# RTI-Dome-eth.net
KiCad netlist of a schematic drawn in EAGLE
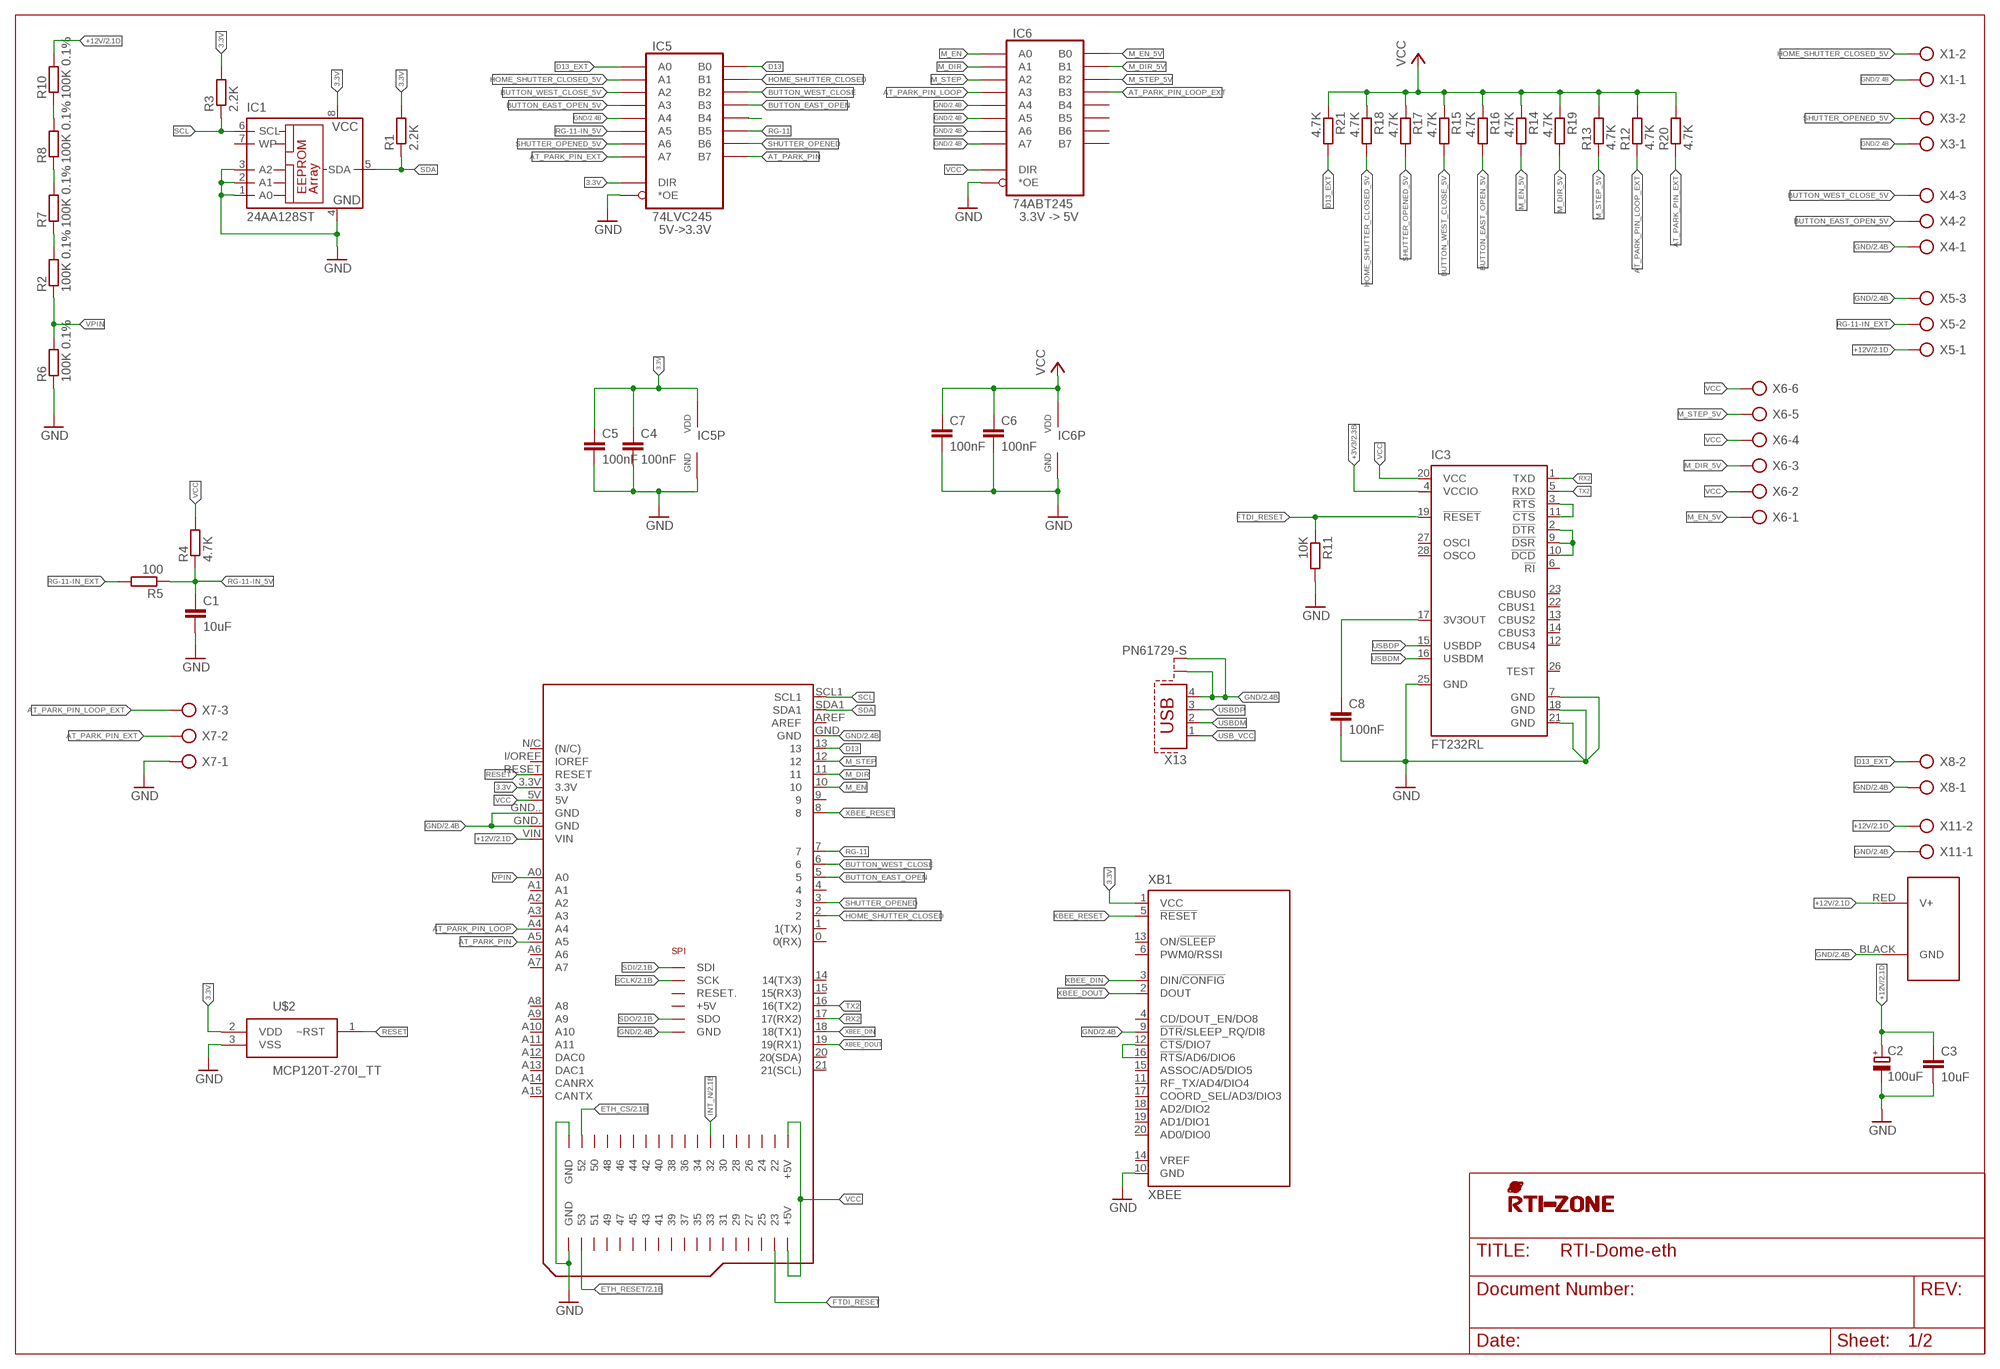
[diagram p0: schematic, sheet 1]
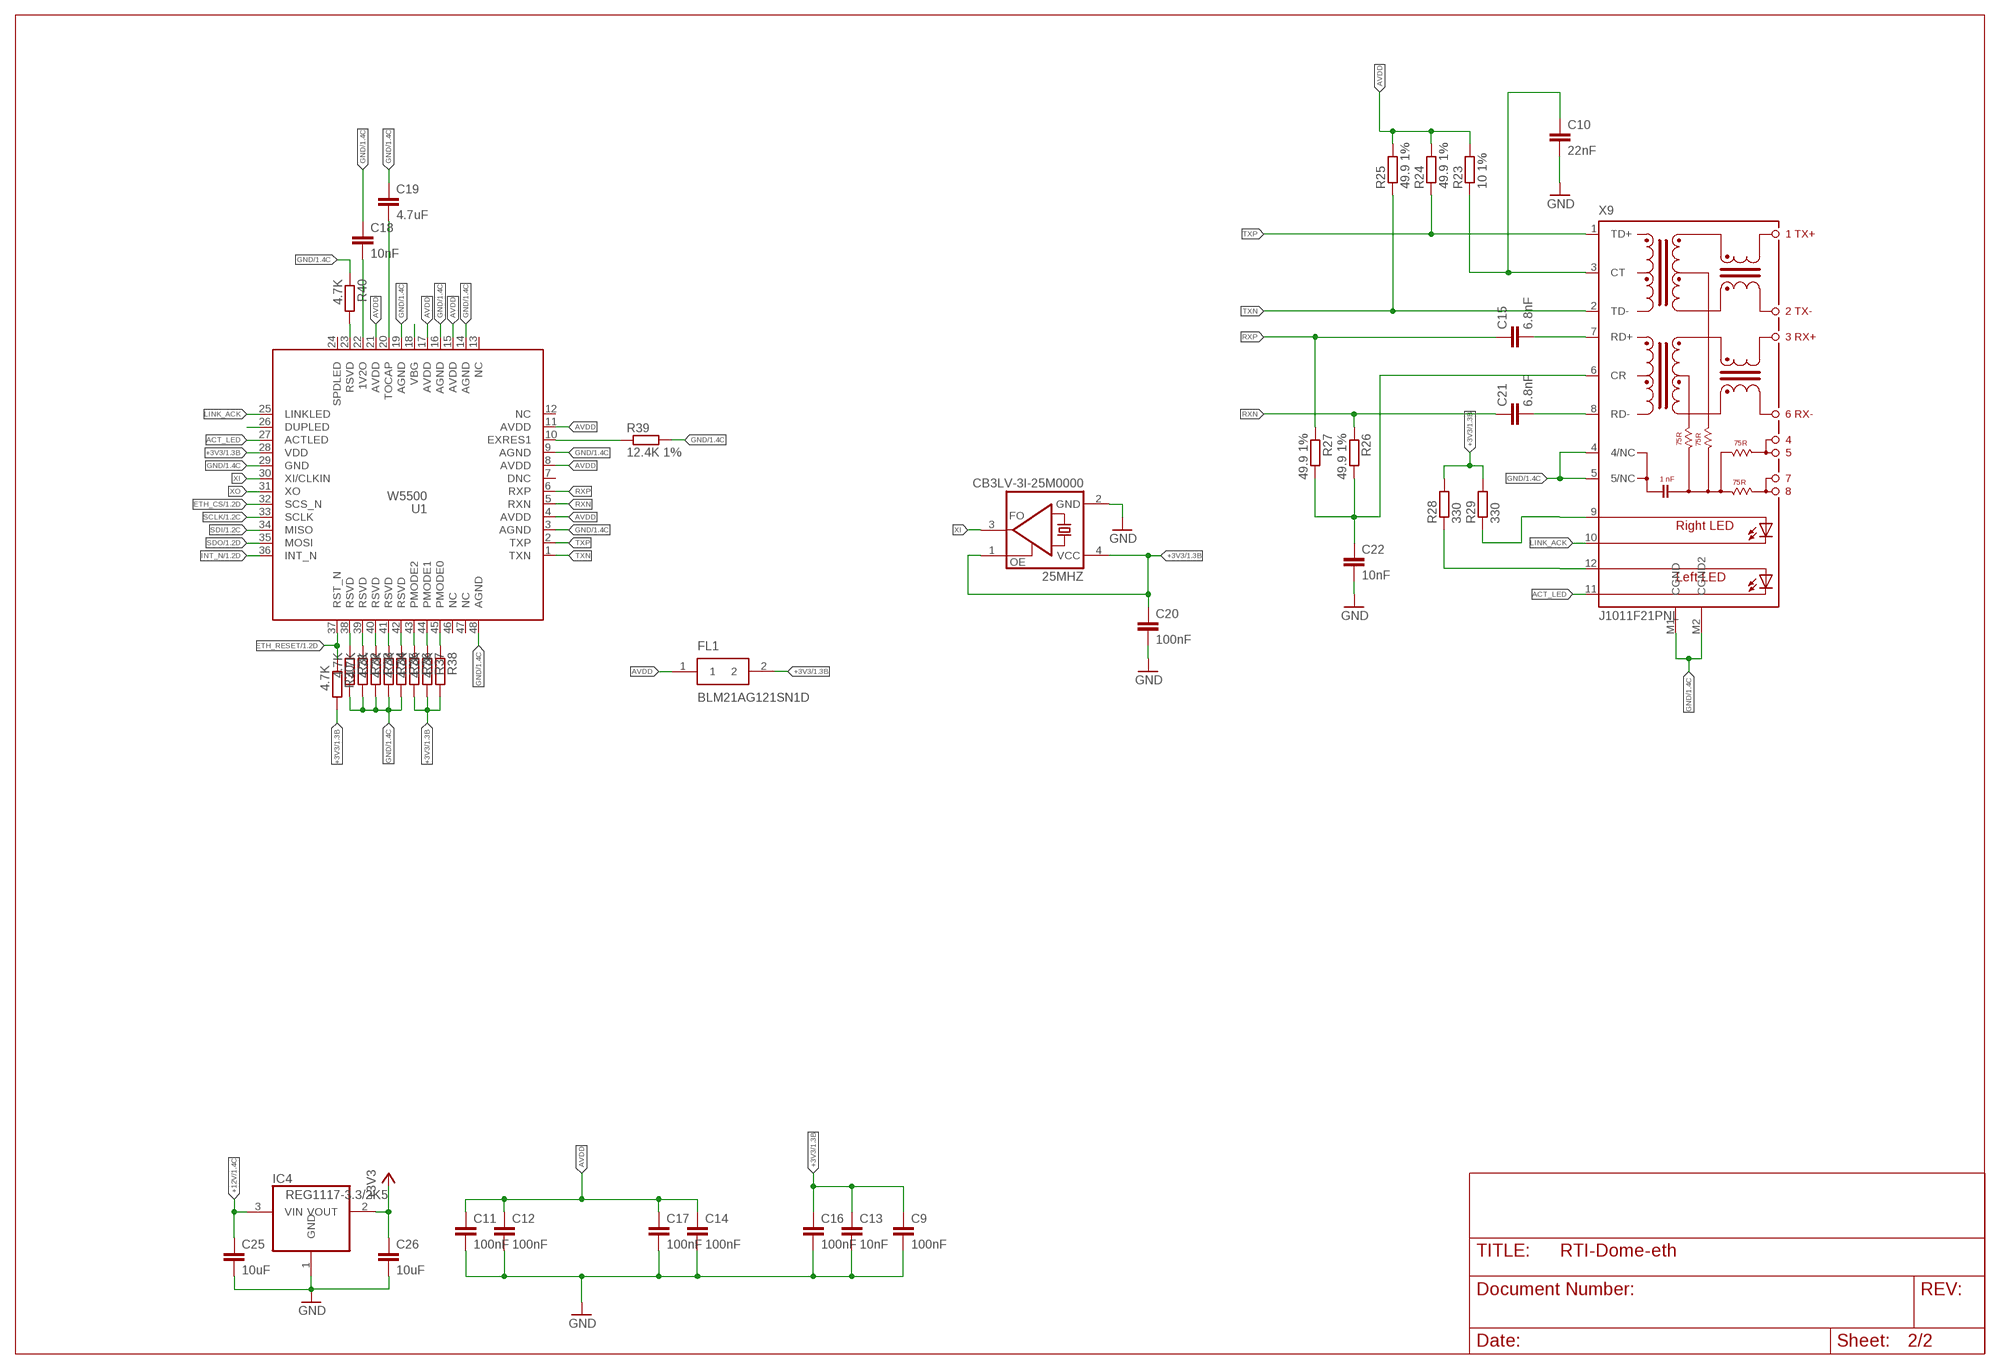
[diagram p1: schematic, sheet 2]

(export (version "E")
  (design (tool "Eeschema 10.0.6"))
  (components
    (comp (ref "25MHZ")
      (value "CB3LV-3I-25M0000")
      (footprint "eagle-import:SMD-7050_4P")
      (libsource (lib "eagle-import") (part "CB3LV-OSCILATOR"))
    )
    (comp (ref "C9")
      (value "100nF")
      (footprint "eagle-import:C0805")
      (fields (field (name "MPN") "0805YD104KAT2A"))
      (libsource (lib "eagle-import") (part "C-EU'0805'"))
    )
    (comp (ref "C10")
      (value "22nF")
      (footprint "eagle-import:C0805")
      (fields (field (name "MPN") "CC0805JRX7R8BB223"))
      (libsource (lib "eagle-import") (part "C-EU'0805'"))
    )
    (comp (ref "C11")
      (value "100nF")
      (footprint "eagle-import:C0805")
      (fields (field (name "MPN") "0805YD104KAT2A"))
      (libsource (lib "eagle-import") (part "C-EU'0805'"))
    )
    (comp (ref "C12")
      (value "100nF")
      (footprint "eagle-import:C0805")
      (fields (field (name "MPN") "0805YD104KAT2A"))
      (libsource (lib "eagle-import") (part "C-EU'0805'"))
    )
    (comp (ref "C13")
      (value "10nF")
      (footprint "eagle-import:C0805")
      (fields (field (name "MPN") " CC0805KRX7R9BB103"))
      (libsource (lib "eagle-import") (part "C-EU'0805'"))
    )
    (comp (ref "C14")
      (value "100nF")
      (footprint "eagle-import:C0805")
      (fields (field (name "MPN") "0805YD104KAT2A"))
      (libsource (lib "eagle-import") (part "C-EU'0805'"))
    )
    (comp (ref "C15")
      (value "6.8nF")
      (footprint "eagle-import:C0805")
      (fields (field (name "MPN") "C0805C682F4HACTU"))
      (libsource (lib "eagle-import") (part "C-EU'0805'"))
    )
    (comp (ref "C16")
      (value "100nF")
      (footprint "eagle-import:C0805")
      (fields (field (name "MPN") "0805YD104KAT2A"))
      (libsource (lib "eagle-import") (part "C-EU'0805'"))
    )
    (comp (ref "C17")
      (value "100nF")
      (footprint "eagle-import:C0805")
      (fields (field (name "MPN") "0805YD104KAT2A"))
      (libsource (lib "eagle-import") (part "C-EU'0805'"))
    )
    (comp (ref "C18")
      (value "10nF")
      (footprint "eagle-import:C0805")
      (fields (field (name "MPN") " CC0805KRX7R9BB103"))
      (libsource (lib "eagle-import") (part "C-EU'0805'"))
    )
    (comp (ref "C19")
      (value "4.7uF")
      (footprint "eagle-import:C0805")
      (fields (field (name "MPN") "C0805C475J3RACTU"))
      (libsource (lib "eagle-import") (part "C-EU'0805'"))
    )
    (comp (ref "C20")
      (value "100nF")
      (footprint "eagle-import:C0805")
      (fields (field (name "MPN") "0805YD104KAT2A"))
      (libsource (lib "eagle-import") (part "C-EU'0805'"))
    )
    (comp (ref "C21")
      (value "6.8nF")
      (footprint "eagle-import:C0805")
      (fields (field (name "MPN") "C0805C682F4HACTU"))
      (libsource (lib "eagle-import") (part "C-EU'0805'"))
    )
    (comp (ref "C22")
      (value "10nF")
      (footprint "eagle-import:C0805")
      (fields (field (name "MPN") " CC0805KRX7R9BB103"))
      (libsource (lib "eagle-import") (part "C-EU'0805'"))
    )
    (comp (ref "C25")
      (value "10uF")
      (footprint "eagle-import:C0805")
      (fields (field (name "MPN") "CC0805KKX5R8BB106"))
      (libsource (lib "eagle-import") (part "C-EU'0805'"))
    )
    (comp (ref "C26")
      (value "10uF")
      (footprint "eagle-import:C0805")
      (fields (field (name "MPN") "CC0805KKX5R8BB106"))
      (libsource (lib "eagle-import") (part "C-EU'0805'"))
    )
    (comp (ref "FL1")
      (value "BLM21AG121SN1D")
      (footprint "eagle-import:L0805")
      (libsource (lib "eagle-import") (part "BLM21AG121SN1D"))
    )
    (comp (ref "IC4")
      (value "REG1117-3.3/2K5")
      (footprint "eagle-import:SOT223")
      (fields (field (name "MPN") "REG1117") (field (name "MPN_1") "REG1117-3.3/2K5"))
      (libsource (lib "eagle-import") (part "REG1117"))
    )
    (comp (ref "R23")
      (value "10 1%")
      (footprint "eagle-import:R0805")
      (fields (field (name "MPN") "RT0805FRE1310RL"))
      (libsource (lib "eagle-import") (part "R-EU'0805'"))
    )
    (comp (ref "R24")
      (value "49.9 1%")
      (footprint "eagle-import:R0805")
      (fields (field (name "MPN") "RC0805FR-0749R9L"))
      (libsource (lib "eagle-import") (part "R-EU'0805'"))
    )
    (comp (ref "R25")
      (value "49.9 1%")
      (footprint "eagle-import:R0805")
      (fields (field (name "MPN") "RC0805FR-0749R9L"))
      (libsource (lib "eagle-import") (part "R-EU'0805'"))
    )
    (comp (ref "R26")
      (value "49.9 1%")
      (footprint "eagle-import:R0805")
      (fields (field (name "MPN") "RC0805FR-0749R9L"))
      (libsource (lib "eagle-import") (part "R-EU'0805'"))
    )
    (comp (ref "R27")
      (value "49.9 1%")
      (footprint "eagle-import:R0805")
      (fields (field (name "MPN") "RC0805FR-0749R9L"))
      (libsource (lib "eagle-import") (part "R-EU'0805'"))
    )
    (comp (ref "R28")
      (value "330")
      (footprint "eagle-import:R0805")
      (fields (field (name "MPN") " RC0805JR-07330RL"))
      (libsource (lib "eagle-import") (part "R-EU'0805'"))
    )
    (comp (ref "R29")
      (value "330")
      (footprint "eagle-import:R0805")
      (fields (field (name "MPN") " RC0805JR-07330RL"))
      (libsource (lib "eagle-import") (part "R-EU'0805'"))
    )
    (comp (ref "R30")
      (value "4.7K")
      (footprint "eagle-import:R0805")
      (fields (field (name "MPN") "RT0805FRE074K7L"))
      (libsource (lib "eagle-import") (part "R-EU'0805'"))
    )
    (comp (ref "R31")
      (value "4.7K")
      (footprint "eagle-import:R0805")
      (fields (field (name "MPN") "RT0805FRE074K7L"))
      (libsource (lib "eagle-import") (part "R-EU'0805'"))
    )
    (comp (ref "R32")
      (value "4.7K")
      (footprint "eagle-import:R0805")
      (fields (field (name "MPN") "RT0805FRE074K7L"))
      (libsource (lib "eagle-import") (part "R-EU'0805'"))
    )
    (comp (ref "R33")
      (value "4.7K")
      (footprint "eagle-import:R0805")
      (fields (field (name "MPN") "RT0805FRE074K7L"))
      (libsource (lib "eagle-import") (part "R-EU'0805'"))
    )
    (comp (ref "R34")
      (value "4.7K")
      (footprint "eagle-import:R0805")
      (fields (field (name "MPN") "RT0805FRE074K7L"))
      (libsource (lib "eagle-import") (part "R-EU'0805'"))
    )
    (comp (ref "R35")
      (value "4.7K")
      (footprint "eagle-import:R0805")
      (fields (field (name "MPN") "RT0805FRE074K7L"))
      (libsource (lib "eagle-import") (part "R-EU'0805'"))
    )
    (comp (ref "R36")
      (value "4.7K")
      (footprint "eagle-import:R0805")
      (fields (field (name "MPN") "RT0805FRE074K7L"))
      (libsource (lib "eagle-import") (part "R-EU'0805'"))
    )
    (comp (ref "R37")
      (value "4.7K")
      (footprint "eagle-import:R0805")
      (fields (field (name "MPN") "RT0805FRE074K7L"))
      (libsource (lib "eagle-import") (part "R-EU'0805'"))
    )
    (comp (ref "R38")
      (value "4.7K")
      (footprint "eagle-import:R0805")
      (fields (field (name "MPN") "RT0805FRE074K7L"))
      (libsource (lib "eagle-import") (part "R-EU'0805'"))
    )
    (comp (ref "R39")
      (value "12.4K 1%")
      (footprint "eagle-import:R0805")
      (fields (field (name "MPN") "RC0805FR-0712K4L"))
      (libsource (lib "eagle-import") (part "R-EU'0805'"))
    )
    (comp (ref "R40")
      (value "4.7K")
      (footprint "eagle-import:R0805")
      (fields (field (name "MPN") "RT0805FRE074K7L"))
      (libsource (lib "eagle-import") (part "R-EU'0805'"))
    )
    (comp (ref "U1")
      (value "W5500")
      (footprint "eagle-import:LQFP48")
      (libsource (lib "eagle-import") (part "W5500"))
    )
    (comp (ref "X9")
      (value "J1011F21PNL")
      (footprint "eagle-import:J1011F21PNL")
      (fields (field (name "MPN") "J1011F21PNL"))
      (libsource (lib "eagle-import") (part "J1011F21PNL"))
    )
    (comp (ref "C1")
      (value "10uF")
      (footprint "eagle-import:C0805")
      (fields (field (name "MPN") "CC0805KKX5R8BB106"))
      (libsource (lib "eagle-import") (part "C-EU'0805'"))
    )
    (comp (ref "C2")
      (value "100uF")
      (footprint "eagle-import:UD-10X10_NICHICON")
      (fields (field (name "MPN") "MAL215099804E3"))
      (libsource (lib "eagle-import") (part "CPOL-EU"))
    )
    (comp (ref "C3")
      (value "10uF")
      (footprint "eagle-import:C0805")
      (fields (field (name "MPN") "CC0805KKX5R8BB106"))
      (libsource (lib "eagle-import") (part "C-EU'0805'"))
    )
    (comp (ref "C4")
      (value "100nF")
      (footprint "eagle-import:C0805")
      (fields (field (name "MPN") "0805YD104KAT2A"))
      (libsource (lib "eagle-import") (part "C-EU'0805'"))
    )
    (comp (ref "C5")
      (value "100nF")
      (footprint "eagle-import:C0805")
      (fields (field (name "MPN") "0805YD104KAT2A"))
      (libsource (lib "eagle-import") (part "C-EU'0805'"))
    )
    (comp (ref "C6")
      (value "100nF")
      (footprint "eagle-import:C0805")
      (fields (field (name "MPN") "0805YD104KAT2A"))
      (libsource (lib "eagle-import") (part "C-EU'0805'"))
    )
    (comp (ref "C7")
      (value "100nF")
      (footprint "eagle-import:C0805")
      (fields (field (name "MPN") "0805YD104KAT2A"))
      (libsource (lib "eagle-import") (part "C-EU'0805'"))
    )
    (comp (ref "C8")
      (value "100nF")
      (footprint "eagle-import:C0805")
      (fields (field (name "MPN") "0805YD104KAT2A"))
      (libsource (lib "eagle-import") (part "C-EU'0805'"))
    )
    (comp (ref "IC1")
      (value "24AA128ST")
      (footprint "eagle-import:TSSOP8")
      (fields (field (name "MF") "MICROCHIP") (field (name "MPN") "24AA128-I/ST"))
      (libsource (lib "eagle-import") (part "24STAA128"))
    )
    (comp (ref "IC3")
      (value "FT232RL")
      (footprint "eagle-import:SSOP28")
      (fields (field (name "MPN") "FT232RL-REEL"))
      (libsource (lib "eagle-import") (part "FT232RL"))
    )
    (comp (ref "IC5")
      (value "74LVC245")
      (footprint "eagle-import:TSSOP20")
      (fields (field (name "MPN") "74LVC245APW,112"))
      (libsource (lib "eagle-import") (part "74245LVC"))
    )
    (comp (ref "IC6")
      (value "74ABT245")
      (footprint "eagle-import:TSSOP20")
      (fields (field (name "MPN") "74ABT245PW,112"))
      (libsource (lib "eagle-import") (part "74245ABT"))
    )
    (comp (ref "J1")
      (value "POWERPOLE_POWER45A")
      (footprint "eagle-import:POWERPOLE_PAIR_45A")
      (libsource (lib "eagle-import") (part "POWERPOLE_POWER45A"))
    )
    (comp (ref "R1")
      (value "2.2K")
      (footprint "eagle-import:R0805")
      (fields (field (name "MPN") "RT0805FRE071KL"))
      (libsource (lib "eagle-import") (part "R-EU'0805'"))
    )
    (comp (ref "R2")
      (value "100K 0.1%")
      (footprint "eagle-import:R0805")
      (fields (field (name "MPN") "AT0805BRD07100KL"))
      (libsource (lib "eagle-import") (part "R-EU'0805'"))
    )
    (comp (ref "R3")
      (value "2.2K")
      (footprint "eagle-import:R0805")
      (fields (field (name "MPN") "RT0805FRE071KL"))
      (libsource (lib "eagle-import") (part "R-EU'0805'"))
    )
    (comp (ref "R4")
      (value "4.7K")
      (footprint "eagle-import:R0805")
      (fields (field (name "MPN") "RT0805FRE074K7L"))
      (libsource (lib "eagle-import") (part "R-EU'0805'"))
    )
    (comp (ref "R5")
      (value "100")
      (footprint "eagle-import:R0805")
      (fields (field (name "MPN") "RT0805FRD07100RL"))
      (libsource (lib "eagle-import") (part "R-EU'0805'"))
    )
    (comp (ref "R6")
      (value "100K 0.1%")
      (footprint "eagle-import:R0805")
      (fields (field (name "MPN") "AT0805BRD07100KL"))
      (libsource (lib "eagle-import") (part "R-EU'0805'"))
    )
    (comp (ref "R7")
      (value "100K 0.1%")
      (footprint "eagle-import:R0805")
      (fields (field (name "MPN") "AT0805BRD07100KL"))
      (libsource (lib "eagle-import") (part "R-EU'0805'"))
    )
    (comp (ref "R8")
      (value "100K 0.1%")
      (footprint "eagle-import:R0805")
      (fields (field (name "MPN") "AT0805BRD07100KL"))
      (libsource (lib "eagle-import") (part "R-EU'0805'"))
    )
    (comp (ref "R10")
      (value "100K 0.1%")
      (footprint "eagle-import:R0805")
      (fields (field (name "MPN") "AT0805BRD07100KL"))
      (libsource (lib "eagle-import") (part "R-EU'0805'"))
    )
    (comp (ref "R11")
      (value "10K")
      (footprint "eagle-import:R0805")
      (fields (field (name "MPN") "RT0805FRE0710KL"))
      (libsource (lib "eagle-import") (part "R-EU'0805'"))
    )
    (comp (ref "R12")
      (value "4.7K")
      (footprint "eagle-import:R0805")
      (fields (field (name "MPN") "RT0805FRE074K7L"))
      (libsource (lib "eagle-import") (part "R-EU'0805'"))
    )
    (comp (ref "R13")
      (value "4.7K")
      (footprint "eagle-import:R0805")
      (fields (field (name "MPN") "RT0805FRE074K7L"))
      (libsource (lib "eagle-import") (part "R-EU'0805'"))
    )
    (comp (ref "R14")
      (value "4.7K")
      (footprint "eagle-import:R0805")
      (fields (field (name "MPN") "RT0805FRE074K7L"))
      (libsource (lib "eagle-import") (part "R-EU'0805'"))
    )
    (comp (ref "R15")
      (value "4.7K")
      (footprint "eagle-import:R0805")
      (fields (field (name "MPN") "RT0805FRE074K7L"))
      (libsource (lib "eagle-import") (part "R-EU'0805'"))
    )
    (comp (ref "R16")
      (value "4.7K")
      (footprint "eagle-import:R0805")
      (fields (field (name "MPN") "RT0805FRE074K7L"))
      (libsource (lib "eagle-import") (part "R-EU'0805'"))
    )
    (comp (ref "R17")
      (value "4.7K")
      (footprint "eagle-import:R0805")
      (fields (field (name "MPN") "RT0805FRE074K7L"))
      (libsource (lib "eagle-import") (part "R-EU'0805'"))
    )
    (comp (ref "R18")
      (value "4.7K")
      (footprint "eagle-import:R0805")
      (fields (field (name "MPN") "RT0805FRE074K7L"))
      (libsource (lib "eagle-import") (part "R-EU'0805'"))
    )
    (comp (ref "R19")
      (value "4.7K")
      (footprint "eagle-import:R0805")
      (fields (field (name "MPN") "RT0805FRE074K7L"))
      (libsource (lib "eagle-import") (part "R-EU'0805'"))
    )
    (comp (ref "R20")
      (value "4.7K")
      (footprint "eagle-import:R0805")
      (fields (field (name "MPN") "RT0805FRE074K7L"))
      (libsource (lib "eagle-import") (part "R-EU'0805'"))
    )
    (comp (ref "R21")
      (value "4.7K")
      (footprint "eagle-import:R0805")
      (fields (field (name "MPN") "RT0805FRE074K7L"))
      (libsource (lib "eagle-import") (part "R-EU'0805'"))
    )
    (comp (ref "U$1")
      (value "ARDUINO_DUE_SHIELD_FULL")
      (footprint "eagle-import:ARDUINO_DUE_SHIELD_FULL")
      (libsource (lib "eagle-import") (part "ARDUINO_DUE_SHIELD_FULL"))
    )
    (comp (ref "U$2")
      (value "MCP120T-270I_TT")
      (footprint "eagle-import:SOT95P237X112-3N")
      (fields
        (field (name "MANUFACTURER_PART_NUMBER") "MCP120T-270I/TT")
        (field (name "MOUSER_PART_NUMBER") "579-MCP120T-270I/TT")
      )
      (libsource (lib "eagle-import") (part "MCP120T-270I_TT"))
    )
    (comp (ref "U$4")
      (value "RTI-LOGO_BIG")
      (footprint "eagle-import:LOGO_BIG")
      (libsource (lib "eagle-import") (part "RTI-LOGO_BIG"))
    )
    (comp (ref "X1")
      (value "AK500/2")
      (footprint "eagle-import:AK500_2")
      (fields (field (name "MPN") "691101710002"))
      (libsource (lib "eagle-import") (part "AK500/2"))
    )
    (comp (ref "X3")
      (value "AK500/2")
      (footprint "eagle-import:AK500_2")
      (fields (field (name "MPN") "691101710002"))
      (libsource (lib "eagle-import") (part "AK500/2"))
    )
    (comp (ref "X4")
      (value "AK500/3")
      (footprint "eagle-import:AK500_3")
      (fields (field (name "MPN") "691101710003"))
      (libsource (lib "eagle-import") (part "AK500/3"))
    )
    (comp (ref "X5")
      (value "AK500/3")
      (footprint "eagle-import:AK500_3")
      (fields (field (name "MPN") "691101710003"))
      (libsource (lib "eagle-import") (part "AK500/3"))
    )
    (comp (ref "X6")
      (value "AK500/6")
      (footprint "eagle-import:AK500_6")
      (fields (field (name "MPN") "30.706"))
      (libsource (lib "eagle-import") (part "AK500/6"))
    )
    (comp (ref "X7")
      (value "AK500/3")
      (footprint "eagle-import:AK500_3")
      (fields (field (name "MPN") "691101710003"))
      (libsource (lib "eagle-import") (part "AK500/3"))
    )
    (comp (ref "X8")
      (value "AK500/2")
      (footprint "eagle-import:AK500_2")
      (fields (field (name "MPN") "691101710002"))
      (libsource (lib "eagle-import") (part "AK500/2"))
    )
    (comp (ref "X11")
      (value "AK500/2")
      (footprint "eagle-import:AK500_2")
      (fields (field (name "MPN") "691101710002"))
      (libsource (lib "eagle-import") (part "AK500/2"))
    )
    (comp (ref "X13")
      (value "PN61729-S")
      (footprint "eagle-import:PN61729-S")
      (fields (field (name "MPN") "SS-52300-001"))
      (libsource (lib "eagle-import") (part "PN61729-S"))
    )
    (comp (ref "XB1")
      (value "XBEE")
      (footprint "eagle-import:XBEE")
      (fields (field (name "MPN") "XBP24-Z7UIT-004"))
      (libsource (lib "eagle-import") (part "XBEE"))
    )
  )
  (nets
    (net (code "1") (name "+3V3") (class "Default")
      (node (ref "25MHZ") (pin "1") (pinfunction "OE_1") (pintype "input"))
      (node (ref "25MHZ") (pin "4") (pinfunction "VDD_4") (pintype "power_in"))
      (node (ref "C13") (pin "1") (pinfunction "1_1") (pintype "passive"))
      (node (ref "C16") (pin "1") (pinfunction "1_1") (pintype "passive"))
      (node (ref "C20") (pin "1") (pinfunction "1_1") (pintype "passive"))
      (node (ref "C26") (pin "1") (pinfunction "1_1") (pintype "passive"))
      (node (ref "C9") (pin "1") (pinfunction "1_1") (pintype "passive"))
      (node (ref "FL1") (pin "2") (pinfunction "2_2") (pintype "bidirectional"))
      (node (ref "IC3") (pin "4") (pinfunction "VCCIO_4") (pintype "power_in"))
      (node (ref "IC4") (pin "2") (pinfunction "VOUT_2") (pintype "output"))
      (node (ref "R28") (pin "2") (pinfunction "2_2") (pintype "passive"))
      (node (ref "R29") (pin "2") (pinfunction "2_2") (pintype "passive"))
      (node (ref "R30") (pin "2") (pinfunction "2_2") (pintype "passive"))
      (node (ref "R36") (pin "2") (pinfunction "2_2") (pintype "passive"))
      (node (ref "R37") (pin "2") (pinfunction "2_2") (pintype "passive"))
      (node (ref "R38") (pin "2") (pinfunction "2_2") (pintype "passive"))
      (node (ref "U1") (pin "28") (pinfunction "VDD_28") (pintype "passive"))
    )
    (net (code "2") (name "+5V") (class "Default")
      (node (ref "U$1") (pin "+5V_") (pinfunction "+5V_+5V_") (pintype "power_in"))
    )
    (net (code "3") (name "+12V") (class "Default")
      (node (ref "C2") (pin "+") (pinfunction "+_+") (pintype "passive"))
      (node (ref "C25") (pin "1") (pinfunction "1_1") (pintype "passive"))
      (node (ref "C3") (pin "1") (pinfunction "1_1") (pintype "passive"))
      (node (ref "IC4") (pin "3") (pinfunction "VIN_3") (pintype "input"))
      (node (ref "J1") (pin "RED") (pinfunction "V+_RED") (pintype "power_in"))
      (node (ref "R10") (pin "2") (pinfunction "2_2") (pintype "passive"))
      (node (ref "U$1") (pin "VIN") (pinfunction "VIN_VIN") (pintype "power_in"))
      (node (ref "X11") (pin "2") (pinfunction "KL_2") (pintype "passive"))
      (node (ref "X5") (pin "1") (pinfunction "KL_1") (pintype "passive"))
    )
    (net (code "4") (name "3.3V") (class "Default")
      (node (ref "C4") (pin "1") (pinfunction "1_1") (pintype "passive"))
      (node (ref "C5") (pin "1") (pinfunction "1_1") (pintype "passive"))
      (node (ref "IC1") (pin "8") (pinfunction "VCC_8") (pintype "power_in"))
      (node (ref "IC5") (pin "P$1") (pinfunction "DIR_P$1") (pintype "input"))
      (node (ref "IC5") (pin "P$20") (pinfunction "VDD_P$20") (pintype "power_in"))
      (node (ref "R1") (pin "2") (pinfunction "2_2") (pintype "passive"))
      (node (ref "R3") (pin "2") (pinfunction "2_2") (pintype "passive"))
      (node (ref "U$1") (pin "3.3V") (pinfunction "3.3V_3.3V") (pintype "power_in"))
      (node (ref "U$2") (pin "2") (pinfunction "VDD_2") (pintype "bidirectional"))
      (node (ref "XB1") (pin "1") (pinfunction "VCC_1") (pintype "power_in"))
    )
    (net (code "5") (name "ACT_LED") (class "Default")
      (node (ref "U1") (pin "27") (pinfunction "ACTLED_27") (pintype "passive"))
      (node (ref "X9") (pin "11") (pinfunction "C-L_11") (pintype "passive"))
    )
    (net (code "6") (name "AT_PARK_PIN") (class "Default")
      (node (ref "IC5") (pin "P$11") (pinfunction "B7_P$11") (pintype "bidirectional"))
      (node (ref "U$1") (pin "A5") (pinfunction "A5_A5") (pintype "bidirectional"))
    )
    (net (code "7") (name "AT_PARK_PIN_EXT") (class "Default")
      (node (ref "IC5") (pin "P$9") (pinfunction "A7_P$9") (pintype "bidirectional"))
      (node (ref "R20") (pin "1") (pinfunction "1_1") (pintype "passive"))
      (node (ref "X7") (pin "2") (pinfunction "KL_2") (pintype "passive"))
    )
    (net (code "8") (name "AT_PARK_PIN_LOOP") (class "Default")
      (node (ref "IC6") (pin "P$5") (pinfunction "A3_P$5") (pintype "bidirectional"))
      (node (ref "U$1") (pin "A4") (pinfunction "A4_A4") (pintype "bidirectional"))
    )
    (net (code "9") (name "AT_PARK_PIN_LOOP_EXT") (class "Default")
      (node (ref "IC6") (pin "P$15") (pinfunction "B3_P$15") (pintype "bidirectional"))
      (node (ref "R12") (pin "1") (pinfunction "1_1") (pintype "passive"))
      (node (ref "X7") (pin "3") (pinfunction "KL_3") (pintype "passive"))
    )
    (net (code "10") (name "AVDD") (class "Default")
      (node (ref "C11") (pin "1") (pinfunction "1_1") (pintype "passive"))
      (node (ref "C12") (pin "1") (pinfunction "1_1") (pintype "passive"))
      (node (ref "C14") (pin "1") (pinfunction "1_1") (pintype "passive"))
      (node (ref "C17") (pin "1") (pinfunction "1_1") (pintype "passive"))
      (node (ref "FL1") (pin "1") (pinfunction "1_1") (pintype "bidirectional"))
      (node (ref "R23") (pin "2") (pinfunction "2_2") (pintype "passive"))
      (node (ref "R24") (pin "2") (pinfunction "2_2") (pintype "passive"))
      (node (ref "R25") (pin "2") (pinfunction "2_2") (pintype "passive"))
      (node (ref "U1") (pin "11") (pinfunction "AVDD_11") (pintype "passive"))
      (node (ref "U1") (pin "15") (pinfunction "AVDD_15") (pintype "passive"))
      (node (ref "U1") (pin "17") (pinfunction "AVDD_17") (pintype "passive"))
      (node (ref "U1") (pin "21") (pinfunction "AVDD_21") (pintype "passive"))
      (node (ref "U1") (pin "4") (pinfunction "AVDD_4") (pintype "passive"))
      (node (ref "U1") (pin "8") (pinfunction "AVDD_8") (pintype "passive"))
    )
    (net (code "11") (name "BUTTON_EAST_OPEN") (class "Default")
      (node (ref "IC5") (pin "P$15") (pinfunction "B3_P$15") (pintype "bidirectional"))
      (node (ref "U$1") (pin "5") (pinfunction "5_5") (pintype "bidirectional"))
    )
    (net (code "12") (name "BUTTON_EAST_OPEN_5V") (class "Default")
      (node (ref "IC5") (pin "P$5") (pinfunction "A3_P$5") (pintype "bidirectional"))
      (node (ref "R16") (pin "2") (pinfunction "2_2") (pintype "passive"))
      (node (ref "X4") (pin "2") (pinfunction "KL_2") (pintype "passive"))
    )
    (net (code "13") (name "BUTTON_WEST_CLOSE") (class "Default")
      (node (ref "IC5") (pin "P$16") (pinfunction "B2_P$16") (pintype "bidirectional"))
      (node (ref "U$1") (pin "6") (pinfunction "6_6") (pintype "bidirectional"))
    )
    (net (code "14") (name "BUTTON_WEST_CLOSE_5V") (class "Default")
      (node (ref "IC5") (pin "P$4") (pinfunction "A2_P$4") (pintype "bidirectional"))
      (node (ref "R15") (pin "2") (pinfunction "2_2") (pintype "passive"))
      (node (ref "X4") (pin "3") (pinfunction "KL_3") (pintype "passive"))
    )
    (net (code "15") (name "D13") (class "Default")
      (node (ref "IC5") (pin "P$18") (pinfunction "B0_P$18") (pintype "bidirectional"))
      (node (ref "U$1") (pin "13") (pinfunction "13_13") (pintype "bidirectional"))
    )
    (net (code "16") (name "D13_EXT") (class "Default")
      (node (ref "IC5") (pin "P$2") (pinfunction "A0_P$2") (pintype "bidirectional"))
      (node (ref "R21") (pin "2") (pinfunction "2_2") (pintype "passive"))
      (node (ref "X8") (pin "2") (pinfunction "KL_2") (pintype "passive"))
    )
    (net (code "17") (name "ETH_CS") (class "Default")
      (node (ref "U$1") (pin "52") (pinfunction "52_52") (pintype "bidirectional"))
      (node (ref "U1") (pin "32") (pinfunction "SCS_N_32") (pintype "passive"))
    )
    (net (code "18") (name "ETH_RESET") (class "Default")
      (node (ref "R30") (pin "1") (pinfunction "1_1") (pintype "passive"))
      (node (ref "U$1") (pin "53") (pinfunction "53_53") (pintype "bidirectional"))
      (node (ref "U1") (pin "37") (pinfunction "RST_N_37") (pintype "passive"))
    )
    (net (code "19") (name "FTDI_RESET") (class "Default")
      (node (ref "IC3") (pin "19") (pinfunction "~{RESET}_19") (pintype "input"))
      (node (ref "R11") (pin "1") (pinfunction "1_1") (pintype "passive"))
      (node (ref "U$1") (pin "23") (pinfunction "23_23") (pintype "bidirectional"))
    )
    (net (code "20") (name "GND") (class "Default")
      (node (ref "25MHZ") (pin "2") (pinfunction "GND_2") (pintype "power_in"))
      (node (ref "C1") (pin "2") (pinfunction "2_2") (pintype "passive"))
      (node (ref "C10") (pin "2") (pinfunction "2_2") (pintype "passive"))
      (node (ref "C11") (pin "2") (pinfunction "2_2") (pintype "passive"))
      (node (ref "C12") (pin "2") (pinfunction "2_2") (pintype "passive"))
      (node (ref "C13") (pin "2") (pinfunction "2_2") (pintype "passive"))
      (node (ref "C14") (pin "2") (pinfunction "2_2") (pintype "passive"))
      (node (ref "C16") (pin "2") (pinfunction "2_2") (pintype "passive"))
      (node (ref "C17") (pin "2") (pinfunction "2_2") (pintype "passive"))
      (node (ref "C18") (pin "1") (pinfunction "1_1") (pintype "passive"))
      (node (ref "C19") (pin "1") (pinfunction "1_1") (pintype "passive"))
      (node (ref "C2") (pin "-") (pinfunction "-_-") (pintype "passive"))
      (node (ref "C20") (pin "2") (pinfunction "2_2") (pintype "passive"))
      (node (ref "C22") (pin "2") (pinfunction "2_2") (pintype "passive"))
      (node (ref "C25") (pin "2") (pinfunction "2_2") (pintype "passive"))
      (node (ref "C26") (pin "2") (pinfunction "2_2") (pintype "passive"))
      (node (ref "C3") (pin "2") (pinfunction "2_2") (pintype "passive"))
      (node (ref "C4") (pin "2") (pinfunction "2_2") (pintype "passive"))
      (node (ref "C5") (pin "2") (pinfunction "2_2") (pintype "passive"))
      (node (ref "C6") (pin "2") (pinfunction "2_2") (pintype "passive"))
      (node (ref "C7") (pin "2") (pinfunction "2_2") (pintype "passive"))
      (node (ref "C8") (pin "2") (pinfunction "2_2") (pintype "passive"))
      (node (ref "C9") (pin "2") (pinfunction "2_2") (pintype "passive"))
      (node (ref "IC1") (pin "1") (pinfunction "A0_1") (pintype "input"))
      (node (ref "IC1") (pin "2") (pinfunction "A1_2") (pintype "input"))
      (node (ref "IC1") (pin "3") (pinfunction "A2_3") (pintype "input"))
      (node (ref "IC1") (pin "4") (pinfunction "GND_4") (pintype "power_in"))
      (node (ref "IC3") (pin "18") (pinfunction "GND_18") (pintype "power_in"))
      (node (ref "IC3") (pin "21") (pinfunction "GND_21") (pintype "power_in"))
      (node (ref "IC3") (pin "25") (pinfunction "GND_25") (pintype "power_in"))
      (node (ref "IC3") (pin "7") (pinfunction "GND_7") (pintype "power_in"))
      (node (ref "IC4") (pin "1") (pinfunction "GND_1") (pintype "power_in"))
      (node (ref "IC5") (pin "P$10") (pinfunction "GND_P$10") (pintype "power_in"))
      (node (ref "IC5") (pin "P$19") (pinfunction "*OE_P$19") (pintype "input"))
      (node (ref "IC5") (pin "P$6") (pinfunction "A4_P$6") (pintype "bidirectional"))
      (node (ref "IC6") (pin "P$10") (pinfunction "GND_P$10") (pintype "power_in"))
      (node (ref "IC6") (pin "P$19") (pinfunction "*OE_P$19") (pintype "input"))
      (node (ref "IC6") (pin "P$6") (pinfunction "A4_P$6") (pintype "bidirectional"))
      (node (ref "IC6") (pin "P$7") (pinfunction "A5_P$7") (pintype "bidirectional"))
      (node (ref "IC6") (pin "P$8") (pinfunction "A6_P$8") (pintype "bidirectional"))
      (node (ref "IC6") (pin "P$9") (pinfunction "A7_P$9") (pintype "bidirectional"))
      (node (ref "J1") (pin "BLACK") (pinfunction "GND_BLACK") (pintype "power_in"))
      (node (ref "R11") (pin "2") (pinfunction "2_2") (pintype "passive"))
      (node (ref "R31") (pin "2") (pinfunction "2_2") (pintype "passive"))
      (node (ref "R32") (pin "2") (pinfunction "2_2") (pintype "passive"))
      (node (ref "R33") (pin "2") (pinfunction "2_2") (pintype "passive"))
      (node (ref "R34") (pin "2") (pinfunction "2_2") (pintype "passive"))
      (node (ref "R35") (pin "2") (pinfunction "2_2") (pintype "passive"))
      (node (ref "R39") (pin "2") (pinfunction "2_2") (pintype "passive"))
      (node (ref "R40") (pin "1") (pinfunction "1_1") (pintype "passive"))
      (node (ref "R6") (pin "1") (pinfunction "1_1") (pintype "passive"))
      (node (ref "U$1") (pin "GND") (pinfunction "GND_GND") (pintype "power_in"))
      (node (ref "U$1") (pin "GND.") (pinfunction "GND_GND.") (pintype "power_in"))
      (node (ref "U$1") (pin "GND..") (pinfunction "GND_GND..") (pintype "power_in"))
      (node (ref "U$1") (pin "GND...") (pinfunction "GND_GND...") (pintype "power_in"))
      (node (ref "U$1") (pin "GND....") (pinfunction "GND_GND....") (pintype "power_in"))
      (node (ref "U$1") (pin "GND__") (pinfunction "GND_GND__") (pintype "power_in"))
      (node (ref "U$2") (pin "3") (pinfunction "VSS_3") (pintype "bidirectional"))
      (node (ref "U1") (pin "14") (pinfunction "AGND_14") (pintype "passive"))
      (node (ref "U1") (pin "16") (pinfunction "AGND_16") (pintype "passive"))
      (node (ref "U1") (pin "19") (pinfunction "AGND_19") (pintype "passive"))
      (node (ref "U1") (pin "29") (pinfunction "GND_29") (pintype "passive"))
      (node (ref "U1") (pin "3") (pinfunction "AGND_3") (pintype "passive"))
      (node (ref "U1") (pin "48") (pinfunction "AGND_48") (pintype "passive"))
      (node (ref "U1") (pin "9") (pinfunction "AGND_9") (pintype "passive"))
      (node (ref "X1") (pin "1") (pinfunction "KL_1") (pintype "passive"))
      (node (ref "X11") (pin "1") (pinfunction "KL_1") (pintype "passive"))
      (node (ref "X13") (pin "4") (pinfunction "4_4") (pintype "passive"))
      (node (ref "X13") (pin "S1") (pinfunction "S1_S1") (pintype "passive"))
      (node (ref "X13") (pin "S2") (pinfunction "S2_S2") (pintype "passive"))
      (node (ref "X3") (pin "1") (pinfunction "KL_1") (pintype "passive"))
      (node (ref "X4") (pin "1") (pinfunction "KL_1") (pintype "passive"))
      (node (ref "X5") (pin "3") (pinfunction "KL_3") (pintype "passive"))
      (node (ref "X7") (pin "1") (pinfunction "KL_1") (pintype "passive"))
      (node (ref "X8") (pin "1") (pinfunction "KL_1") (pintype "passive"))
      (node (ref "X9") (pin "4") (pinfunction "4/NC_4") (pintype "input"))
      (node (ref "X9") (pin "5") (pinfunction "5/NC_5") (pintype "input"))
      (node (ref "X9") (pin "M1") (pinfunction "CGND_M1") (pintype "bidirectional"))
      (node (ref "X9") (pin "M2") (pinfunction "CGND2_M2") (pintype "bidirectional"))
      (node (ref "XB1") (pin "10") (pinfunction "GND_10") (pintype "power_in"))
      (node (ref "XB1") (pin "9") (pinfunction "~{DTR}/SLEEP_RQ/DI8_9") (pintype "bidirectional"))
    )
    (net (code "21") (name "HOME_SHUTTER_CLOSED") (class "Default")
      (node (ref "IC5") (pin "P$17") (pinfunction "B1_P$17") (pintype "bidirectional"))
      (node (ref "U$1") (pin "2") (pinfunction "2_2") (pintype "bidirectional"))
    )
    (net (code "22") (name "HOME_SHUTTER_CLOSED_5V") (class "Default")
      (node (ref "IC5") (pin "P$3") (pinfunction "A1_P$3") (pintype "bidirectional"))
      (node (ref "R18") (pin "2") (pinfunction "2_2") (pintype "passive"))
      (node (ref "X1") (pin "2") (pinfunction "KL_2") (pintype "passive"))
    )
    (net (code "23") (name "INT_N") (class "Default")
      (node (ref "U$1") (pin "32") (pinfunction "32_32") (pintype "bidirectional"))
      (node (ref "U1") (pin "36") (pinfunction "INT_N_36") (pintype "passive"))
    )
    (net (code "24") (name "LINK_ACK") (class "Default")
      (node (ref "U1") (pin "25") (pinfunction "LINKLED_25") (pintype "passive"))
      (node (ref "X9") (pin "10") (pinfunction "C-R_10") (pintype "passive"))
    )
    (net (code "25") (name "M_DIR") (class "Default")
      (node (ref "IC6") (pin "P$3") (pinfunction "A1_P$3") (pintype "bidirectional"))
      (node (ref "U$1") (pin "11") (pinfunction "11_11") (pintype "bidirectional"))
    )
    (net (code "26") (name "M_DIR_5V") (class "Default")
      (node (ref "IC6") (pin "P$17") (pinfunction "B1_P$17") (pintype "bidirectional"))
      (node (ref "R19") (pin "2") (pinfunction "2_2") (pintype "passive"))
      (node (ref "X6") (pin "3") (pinfunction "KL_3") (pintype "passive"))
    )
    (net (code "27") (name "M_EN") (class "Default")
      (node (ref "IC6") (pin "P$2") (pinfunction "A0_P$2") (pintype "bidirectional"))
      (node (ref "U$1") (pin "10") (pinfunction "10_10") (pintype "bidirectional"))
    )
    (net (code "28") (name "M_EN_5V") (class "Default")
      (node (ref "IC6") (pin "P$18") (pinfunction "B0_P$18") (pintype "bidirectional"))
      (node (ref "R14") (pin "2") (pinfunction "2_2") (pintype "passive"))
      (node (ref "X6") (pin "1") (pinfunction "KL_1") (pintype "passive"))
    )
    (net (code "29") (name "M_STEP") (class "Default")
      (node (ref "IC6") (pin "P$4") (pinfunction "A2_P$4") (pintype "bidirectional"))
      (node (ref "U$1") (pin "12") (pinfunction "12_12") (pintype "bidirectional"))
    )
    (net (code "30") (name "M_STEP_5V") (class "Default")
      (node (ref "IC6") (pin "P$16") (pinfunction "B2_P$16") (pintype "bidirectional"))
      (node (ref "R13") (pin "1") (pinfunction "1_1") (pintype "passive"))
      (node (ref "X6") (pin "5") (pinfunction "KL_5") (pintype "passive"))
    )
    (net (code "31") (name "Net-(IC3-3V3OUT)") (class "Default")
      (node (ref "C8") (pin "1") (pinfunction "1_1") (pintype "passive"))
      (node (ref "IC3") (pin "17") (pinfunction "3V3OUT_17") (pintype "output"))
    )
    (net (code "32") (name "Net-(IC3-~{CTS})") (class "Default")
      (node (ref "IC3") (pin "11") (pinfunction "~{CTS}_11") (pintype "input"))
      (node (ref "IC3") (pin "3") (pinfunction "~{RTS}_3") (pintype "output"))
    )
    (net (code "33") (name "Net-(IC3-~{DCD})") (class "Default")
      (node (ref "IC3") (pin "10") (pinfunction "~{DCD}_10") (pintype "input"))
      (node (ref "IC3") (pin "2") (pinfunction "~{DTR}_2") (pintype "output"))
      (node (ref "IC3") (pin "9") (pinfunction "~{DSR}_9") (pintype "input"))
    )
    (net (code "34") (name "Net-(R2-Pad2)") (class "Default")
      (node (ref "R2") (pin "2") (pinfunction "2_2") (pintype "passive"))
      (node (ref "R7") (pin "1") (pinfunction "1_1") (pintype "passive"))
    )
    (net (code "35") (name "Net-(R7-Pad2)") (class "Default")
      (node (ref "R7") (pin "2") (pinfunction "2_2") (pintype "passive"))
      (node (ref "R8") (pin "1") (pinfunction "1_1") (pintype "passive"))
    )
    (net (code "36") (name "Net-(R10-Pad1)") (class "Default")
      (node (ref "R10") (pin "1") (pinfunction "1_1") (pintype "passive"))
      (node (ref "R8") (pin "2") (pinfunction "2_2") (pintype "passive"))
    )
    (net (code "37") (name "Net-(R31-Pad1)") (class "Default")
      (node (ref "R31") (pin "1") (pinfunction "1_1") (pintype "passive"))
      (node (ref "U1") (pin "38") (pinfunction "RSVD_38") (pintype "passive"))
    )
    (net (code "38") (name "Net-(R32-Pad1)") (class "Default")
      (node (ref "R32") (pin "1") (pinfunction "1_1") (pintype "passive"))
      (node (ref "U1") (pin "39") (pinfunction "RSVD_39") (pintype "passive"))
    )
    (net (code "39") (name "Net-(R33-Pad1)") (class "Default")
      (node (ref "R33") (pin "1") (pinfunction "1_1") (pintype "passive"))
      (node (ref "U1") (pin "40") (pinfunction "RSVD_40") (pintype "passive"))
    )
    (net (code "40") (name "Net-(R34-Pad1)") (class "Default")
      (node (ref "R34") (pin "1") (pinfunction "1_1") (pintype "passive"))
      (node (ref "U1") (pin "41") (pinfunction "RSVD_41") (pintype "passive"))
    )
    (net (code "41") (name "Net-(R35-Pad1)") (class "Default")
      (node (ref "R35") (pin "1") (pinfunction "1_1") (pintype "passive"))
      (node (ref "U1") (pin "42") (pinfunction "RSVD_42") (pintype "passive"))
    )
    (net (code "42") (name "Net-(R40-Pad2)") (class "Default")
      (node (ref "R40") (pin "2") (pinfunction "2_2") (pintype "passive"))
      (node (ref "U1") (pin "23") (pinfunction "RSVD_23") (pintype "passive"))
    )
    (net (code "43") (name "Net-(U1-1V2O)") (class "Default")
      (node (ref "C18") (pin "2") (pinfunction "2_2") (pintype "passive"))
      (node (ref "U1") (pin "22") (pinfunction "1V2O_22") (pintype "passive"))
    )
    (net (code "44") (name "Net-(U1-EXRES1)") (class "Default")
      (node (ref "R39") (pin "1") (pinfunction "1_1") (pintype "passive"))
      (node (ref "U1") (pin "10") (pinfunction "EXRES1_10") (pintype "passive"))
    )
    (net (code "45") (name "Net-(U1-PMODE0)") (class "Default")
      (node (ref "R38") (pin "1") (pinfunction "1_1") (pintype "passive"))
      (node (ref "U1") (pin "45") (pinfunction "PMODE0_45") (pintype "passive"))
    )
    (net (code "46") (name "Net-(U1-PMODE1)") (class "Default")
      (node (ref "R37") (pin "1") (pinfunction "1_1") (pintype "passive"))
      (node (ref "U1") (pin "44") (pinfunction "PMODE1_44") (pintype "passive"))
    )
    (net (code "47") (name "Net-(U1-PMODE2)") (class "Default")
      (node (ref "R36") (pin "1") (pinfunction "1_1") (pintype "passive"))
      (node (ref "U1") (pin "43") (pinfunction "PMODE2_43") (pintype "passive"))
    )
    (net (code "48") (name "Net-(U1-TOCAP)") (class "Default")
      (node (ref "C19") (pin "2") (pinfunction "2_2") (pintype "passive"))
      (node (ref "U1") (pin "20") (pinfunction "TOCAP_20") (pintype "passive"))
    )
    (net (code "49") (name "Net-(X9-A-R)") (class "Default")
      (node (ref "R29") (pin "1") (pinfunction "1_1") (pintype "passive"))
      (node (ref "X9") (pin "9") (pinfunction "A-R_9") (pintype "passive"))
    )
    (net (code "50") (name "Net-(X9-AL)") (class "Default")
      (node (ref "R28") (pin "1") (pinfunction "1_1") (pintype "passive"))
      (node (ref "X9") (pin "12") (pinfunction "AL_12") (pintype "passive"))
    )
    (net (code "51") (name "Net-(X9-CR)") (class "Default")
      (node (ref "C22") (pin "1") (pinfunction "1_1") (pintype "passive"))
      (node (ref "R26") (pin "2") (pinfunction "2_2") (pintype "passive"))
      (node (ref "R27") (pin "2") (pinfunction "2_2") (pintype "passive"))
      (node (ref "X9") (pin "6") (pinfunction "CR_6") (pintype "input"))
    )
    (net (code "52") (name "Net-(X9-CT)") (class "Default")
      (node (ref "C10") (pin "1") (pinfunction "1_1") (pintype "passive"))
      (node (ref "R23") (pin "1") (pinfunction "1_1") (pintype "passive"))
      (node (ref "X9") (pin "3") (pinfunction "CT_3") (pintype "input"))
    )
    (net (code "53") (name "Net-(X9-RD+)") (class "Default")
      (node (ref "C15") (pin "2") (pinfunction "2_2") (pintype "passive"))
      (node (ref "X9") (pin "7") (pinfunction "RD+_7") (pintype "input"))
    )
    (net (code "54") (name "Net-(X9-RD-)") (class "Default")
      (node (ref "C21") (pin "2") (pinfunction "2_2") (pintype "passive"))
      (node (ref "X9") (pin "8") (pinfunction "RD-_8") (pintype "input"))
    )
    (net (code "55") (name "Net-(XB1-~{CTS}{slash}DIO7)") (class "Default")
      (node (ref "XB1") (pin "12") (pinfunction "~{CTS}/DIO7_12") (pintype "bidirectional"))
      (node (ref "XB1") (pin "16") (pinfunction "~{RTS}/AD6/DIO6_16") (pintype "bidirectional"))
    )
    (net (code "56") (name "RESET") (class "Default")
      (node (ref "U$1") (pin "RESET") (pinfunction "RESET_RESET") (pintype "bidirectional"))
      (node (ref "U$2") (pin "1") (pinfunction "~{RST}_1") (pintype "bidirectional"))
    )
    (net (code "57") (name "RG-11") (class "Default")
      (node (ref "IC5") (pin "P$13") (pinfunction "B5_P$13") (pintype "bidirectional"))
      (node (ref "U$1") (pin "7") (pinfunction "7_7") (pintype "bidirectional"))
    )
    (net (code "58") (name "RG-11-IN_5V") (class "Default")
      (node (ref "C1") (pin "1") (pinfunction "1_1") (pintype "passive"))
      (node (ref "IC5") (pin "P$7") (pinfunction "A5_P$7") (pintype "bidirectional"))
      (node (ref "R4") (pin "1") (pinfunction "1_1") (pintype "passive"))
      (node (ref "R5") (pin "1") (pinfunction "1_1") (pintype "passive"))
    )
    (net (code "59") (name "RG-11-IN_EXT") (class "Default")
      (node (ref "R5") (pin "2") (pinfunction "2_2") (pintype "passive"))
      (node (ref "X5") (pin "2") (pinfunction "KL_2") (pintype "passive"))
    )
    (net (code "60") (name "RX2") (class "Default")
      (node (ref "IC3") (pin "1") (pinfunction "TXD_1") (pintype "output"))
      (node (ref "U$1") (pin "17") (pinfunction "17(RX2)_17") (pintype "bidirectional"))
    )
    (net (code "61") (name "RXN") (class "Default")
      (node (ref "C21") (pin "1") (pinfunction "1_1") (pintype "passive"))
      (node (ref "R26") (pin "1") (pinfunction "1_1") (pintype "passive"))
      (node (ref "U1") (pin "5") (pinfunction "RXN_5") (pintype "passive"))
    )
    (net (code "62") (name "RXP") (class "Default")
      (node (ref "C15") (pin "1") (pinfunction "1_1") (pintype "passive"))
      (node (ref "R27") (pin "1") (pinfunction "1_1") (pintype "passive"))
      (node (ref "U1") (pin "6") (pinfunction "RXP_6") (pintype "passive"))
    )
    (net (code "63") (name "SCL") (class "Default")
      (node (ref "IC1") (pin "6") (pinfunction "SCL_6") (pintype "input"))
      (node (ref "R3") (pin "1") (pinfunction "1_1") (pintype "passive"))
      (node (ref "U$1") (pin "SCL1") (pinfunction "SCL1_SCL1") (pintype "bidirectional"))
    )
    (net (code "64") (name "SCLK") (class "Default")
      (node (ref "U$1") (pin "SCK") (pinfunction "SCK_SCK") (pintype "bidirectional"))
      (node (ref "U1") (pin "33") (pinfunction "SCLK_33") (pintype "passive"))
    )
    (net (code "65") (name "SDA") (class "Default")
      (node (ref "IC1") (pin "5") (pinfunction "SDA_5") (pintype "bidirectional"))
      (node (ref "R1") (pin "1") (pinfunction "1_1") (pintype "passive"))
      (node (ref "U$1") (pin "SDA1") (pinfunction "SDA1_SDA1") (pintype "bidirectional"))
    )
    (net (code "66") (name "SDI") (class "Default")
      (node (ref "U$1") (pin "MISO") (pinfunction "SDI_MISO") (pintype "bidirectional"))
      (node (ref "U1") (pin "34") (pinfunction "MISO_34") (pintype "passive"))
    )
    (net (code "67") (name "SDO") (class "Default")
      (node (ref "U$1") (pin "MOSI") (pinfunction "SDO_MOSI") (pintype "bidirectional"))
      (node (ref "U1") (pin "35") (pinfunction "MOSI_35") (pintype "passive"))
    )
    (net (code "68") (name "SHUTTER_OPENED") (class "Default")
      (node (ref "IC5") (pin "P$12") (pinfunction "B6_P$12") (pintype "bidirectional"))
      (node (ref "U$1") (pin "3") (pinfunction "3_3") (pintype "bidirectional"))
    )
    (net (code "69") (name "SHUTTER_OPENED_5V") (class "Default")
      (node (ref "IC5") (pin "P$8") (pinfunction "A6_P$8") (pintype "bidirectional"))
      (node (ref "R17") (pin "2") (pinfunction "2_2") (pintype "passive"))
      (node (ref "X3") (pin "2") (pinfunction "KL_2") (pintype "passive"))
    )
    (net (code "70") (name "TX2") (class "Default")
      (node (ref "IC3") (pin "5") (pinfunction "RXD_5") (pintype "input"))
      (node (ref "U$1") (pin "16") (pinfunction "16(TX2)_16") (pintype "bidirectional"))
    )
    (net (code "71") (name "TXN") (class "Default")
      (node (ref "R25") (pin "1") (pinfunction "1_1") (pintype "passive"))
      (node (ref "U1") (pin "1") (pinfunction "TXN_1") (pintype "passive"))
      (node (ref "X9") (pin "2") (pinfunction "TD-_2") (pintype "input"))
    )
    (net (code "72") (name "TXP") (class "Default")
      (node (ref "R24") (pin "1") (pinfunction "1_1") (pintype "passive"))
      (node (ref "U1") (pin "2") (pinfunction "TXP_2") (pintype "passive"))
      (node (ref "X9") (pin "1") (pinfunction "TD+_1") (pintype "input"))
    )
    (net (code "73") (name "USBDM") (class "Default")
      (node (ref "IC3") (pin "16") (pinfunction "USBDM_16") (pintype "bidirectional"))
      (node (ref "X13") (pin "2") (pinfunction "2_2") (pintype "passive"))
    )
    (net (code "74") (name "USBDP") (class "Default")
      (node (ref "IC3") (pin "15") (pinfunction "USBDP_15") (pintype "bidirectional"))
      (node (ref "X13") (pin "3") (pinfunction "3_3") (pintype "passive"))
    )
    (net (code "75") (name "USB_VCC") (class "Default")
      (node (ref "X13") (pin "1") (pinfunction "1_1") (pintype "passive"))
    )
    (net (code "76") (name "VCC") (class "Default")
      (node (ref "C6") (pin "1") (pinfunction "1_1") (pintype "passive"))
      (node (ref "C7") (pin "1") (pinfunction "1_1") (pintype "passive"))
      (node (ref "IC3") (pin "20") (pinfunction "VCC_20") (pintype "power_in"))
      (node (ref "IC6") (pin "P$1") (pinfunction "DIR_P$1") (pintype "input"))
      (node (ref "IC6") (pin "P$20") (pinfunction "VDD_P$20") (pintype "power_in"))
      (node (ref "R12") (pin "2") (pinfunction "2_2") (pintype "passive"))
      (node (ref "R13") (pin "2") (pinfunction "2_2") (pintype "passive"))
      (node (ref "R14") (pin "1") (pinfunction "1_1") (pintype "passive"))
      (node (ref "R15") (pin "1") (pinfunction "1_1") (pintype "passive"))
      (node (ref "R16") (pin "1") (pinfunction "1_1") (pintype "passive"))
      (node (ref "R17") (pin "1") (pinfunction "1_1") (pintype "passive"))
      (node (ref "R18") (pin "1") (pinfunction "1_1") (pintype "passive"))
      (node (ref "R19") (pin "1") (pinfunction "1_1") (pintype "passive"))
      (node (ref "R20") (pin "2") (pinfunction "2_2") (pintype "passive"))
      (node (ref "R21") (pin "1") (pinfunction "1_1") (pintype "passive"))
      (node (ref "R4") (pin "2") (pinfunction "2_2") (pintype "passive"))
      (node (ref "U$1") (pin "5V") (pinfunction "5V_5V") (pintype "power_in"))
      (node (ref "U$1") (pin "5V.") (pinfunction "+5V_5V.") (pintype "power_in"))
      (node (ref "U$1") (pin "5V..") (pinfunction "+5V_5V..") (pintype "power_in"))
      (node (ref "X6") (pin "2") (pinfunction "KL_2") (pintype "passive"))
      (node (ref "X6") (pin "4") (pinfunction "KL_4") (pintype "passive"))
      (node (ref "X6") (pin "6") (pinfunction "KL_6") (pintype "passive"))
    )
    (net (code "77") (name "VPIN") (class "Default")
      (node (ref "R2") (pin "1") (pinfunction "1_1") (pintype "passive"))
      (node (ref "R6") (pin "2") (pinfunction "2_2") (pintype "passive"))
      (node (ref "U$1") (pin "A0") (pinfunction "A0_A0") (pintype "bidirectional"))
    )
    (net (code "78") (name "XBEE_DIN") (class "Default")
      (node (ref "U$1") (pin "18") (pinfunction "18(TX1)_18") (pintype "bidirectional"))
      (node (ref "XB1") (pin "3") (pinfunction "DIN/~{CONFIG}_3") (pintype "input"))
    )
    (net (code "79") (name "XBEE_DOUT") (class "Default")
      (node (ref "U$1") (pin "19") (pinfunction "19(RX1)_19") (pintype "bidirectional"))
      (node (ref "XB1") (pin "2") (pinfunction "DOUT_2") (pintype "output"))
    )
    (net (code "80") (name "XBEE_RESET") (class "Default")
      (node (ref "U$1") (pin "8") (pinfunction "8_8") (pintype "bidirectional"))
      (node (ref "XB1") (pin "5") (pinfunction "~{RESET}_5") (pintype "input"))
    )
    (net (code "81") (name "XI") (class "Default")
      (node (ref "25MHZ") (pin "3") (pinfunction "FO_3") (pintype "output"))
      (node (ref "U1") (pin "30") (pinfunction "XI/CLKIN_30") (pintype "passive"))
    )
    (net (code "82") (name "XO") (class "Default")
      (node (ref "U1") (pin "31") (pinfunction "XO_31") (pintype "passive"))
    )
    (net (code "83") (name "unconnected-(IC1-WP-Pad7)") (class "Default")
      (node (ref "IC1") (pin "7") (pinfunction "WP_7") (pintype "input"))
    )
    (net (code "84") (name "unconnected-(IC3-CBUS0-Pad23)") (class "Default")
      (node (ref "IC3") (pin "23") (pinfunction "CBUS0_23") (pintype "bidirectional"))
    )
    (net (code "85") (name "unconnected-(IC3-CBUS1-Pad22)") (class "Default")
      (node (ref "IC3") (pin "22") (pinfunction "CBUS1_22") (pintype "bidirectional"))
    )
    (net (code "86") (name "unconnected-(IC3-CBUS2-Pad13)") (class "Default")
      (node (ref "IC3") (pin "13") (pinfunction "CBUS2_13") (pintype "bidirectional"))
    )
    (net (code "87") (name "unconnected-(IC3-CBUS3-Pad14)") (class "Default")
      (node (ref "IC3") (pin "14") (pinfunction "CBUS3_14") (pintype "bidirectional"))
    )
    (net (code "88") (name "unconnected-(IC3-CBUS4-Pad12)") (class "Default")
      (node (ref "IC3") (pin "12") (pinfunction "CBUS4_12") (pintype "bidirectional"))
    )
    (net (code "89") (name "unconnected-(IC3-OSCI-Pad27)") (class "Default")
      (node (ref "IC3") (pin "27") (pinfunction "OSCI_27") (pintype "input"))
    )
    (net (code "90") (name "unconnected-(IC3-OSCO-Pad28)") (class "Default")
      (node (ref "IC3") (pin "28") (pinfunction "OSCO_28") (pintype "output"))
    )
    (net (code "91") (name "unconnected-(IC3-TEST-Pad26)") (class "Default")
      (node (ref "IC3") (pin "26") (pinfunction "TEST_26") (pintype "input"))
    )
    (net (code "92") (name "unconnected-(IC3-~{RI}-Pad6)") (class "Default")
      (node (ref "IC3") (pin "6") (pinfunction "~{RI}_6") (pintype "input"))
    )
    (net (code "93") (name "unconnected-(IC5A-B4-PadP$14)") (class "Default")
      (node (ref "IC5") (pin "P$14") (pinfunction "B4_P$14") (pintype "bidirectional"))
    )
    (net (code "94") (name "unconnected-(IC6A-B4-PadP$14)") (class "Default")
      (node (ref "IC6") (pin "P$14") (pinfunction "B4_P$14") (pintype "bidirectional"))
    )
    (net (code "95") (name "unconnected-(IC6A-B5-PadP$13)") (class "Default")
      (node (ref "IC6") (pin "P$13") (pinfunction "B5_P$13") (pintype "bidirectional"))
    )
    (net (code "96") (name "unconnected-(IC6A-B6-PadP$12)") (class "Default")
      (node (ref "IC6") (pin "P$12") (pinfunction "B6_P$12") (pintype "bidirectional"))
    )
    (net (code "97") (name "unconnected-(IC6A-B7-PadP$11)") (class "Default")
      (node (ref "IC6") (pin "P$11") (pinfunction "B7_P$11") (pintype "bidirectional"))
    )
    (net (code "98") (name "unconnected-(U$1-(N{slash}C)-PadN{slash}C)") (class "Default")
      (node (ref "U$1") (pin "N/C") (pinfunction "(N/C)_N/C") (pintype "no_connect"))
    )
    (net (code "99") (name "unconnected-(U$1-0(RX)-Pad0)") (class "Default")
      (node (ref "U$1") (pin "0") (pinfunction "0(RX)_0") (pintype "bidirectional"))
    )
    (net (code "100") (name "unconnected-(U$1-1(TX)-Pad1)") (class "Default")
      (node (ref "U$1") (pin "1") (pinfunction "1(TX)_1") (pintype "bidirectional"))
    )
    (net (code "101") (name "unconnected-(U$1-14(TX3)-Pad14)") (class "Default")
      (node (ref "U$1") (pin "14") (pinfunction "14(TX3)_14") (pintype "bidirectional"))
    )
    (net (code "102") (name "unconnected-(U$1-15(RX3)-Pad15)") (class "Default")
      (node (ref "U$1") (pin "15") (pinfunction "15(RX3)_15") (pintype "bidirectional"))
    )
    (net (code "103") (name "unconnected-(U$1-20(SDA)-Pad20)") (class "Default")
      (node (ref "U$1") (pin "20") (pinfunction "20(SDA)_20") (pintype "bidirectional"))
    )
    (net (code "104") (name "unconnected-(U$1-21(SCL)-Pad21)") (class "Default")
      (node (ref "U$1") (pin "21") (pinfunction "21(SCL)_21") (pintype "bidirectional"))
    )
    (net (code "105") (name "unconnected-(U$1-CANRX-PadA14)") (class "Default")
      (node (ref "U$1") (pin "A14") (pinfunction "CANRX_A14") (pintype "bidirectional"))
    )
    (net (code "106") (name "unconnected-(U$1-CANTX-PadA15)") (class "Default")
      (node (ref "U$1") (pin "A15") (pinfunction "CANTX_A15") (pintype "bidirectional"))
    )
    (net (code "107") (name "unconnected-(U$1-DAC0-PadA12)") (class "Default")
      (node (ref "U$1") (pin "A12") (pinfunction "DAC0_A12") (pintype "bidirectional"))
    )
    (net (code "108") (name "unconnected-(U$1-DAC1-PadA13)") (class "Default")
      (node (ref "U$1") (pin "A13") (pinfunction "DAC1_A13") (pintype "bidirectional"))
    )
    (net (code "109") (name "unconnected-(U$1-IOREF-PadI{slash}OREF)") (class "Default")
      (node (ref "U$1") (pin "I/OREF") (pinfunction "IOREF_I/OREF") (pintype "bidirectional"))
    )
    (net (code "110") (name "unconnected-(U$1-Pad4)") (class "Default")
      (node (ref "U$1") (pin "4") (pinfunction "4_4") (pintype "bidirectional"))
    )
    (net (code "111") (name "unconnected-(U$1-Pad9)") (class "Default")
      (node (ref "U$1") (pin "9") (pinfunction "9_9") (pintype "bidirectional"))
    )
    (net (code "112") (name "unconnected-(U$1-Pad22)") (class "Default")
      (node (ref "U$1") (pin "22") (pinfunction "22_22") (pintype "bidirectional"))
    )
    (net (code "113") (name "unconnected-(U$1-Pad24)") (class "Default")
      (node (ref "U$1") (pin "24") (pinfunction "24_24") (pintype "bidirectional"))
    )
    (net (code "114") (name "unconnected-(U$1-Pad25)") (class "Default")
      (node (ref "U$1") (pin "25") (pinfunction "25_25") (pintype "bidirectional"))
    )
    (net (code "115") (name "unconnected-(U$1-Pad26)") (class "Default")
      (node (ref "U$1") (pin "26") (pinfunction "26_26") (pintype "bidirectional"))
    )
    (net (code "116") (name "unconnected-(U$1-Pad27)") (class "Default")
      (node (ref "U$1") (pin "27") (pinfunction "27_27") (pintype "bidirectional"))
    )
    (net (code "117") (name "unconnected-(U$1-Pad28)") (class "Default")
      (node (ref "U$1") (pin "28") (pinfunction "28_28") (pintype "bidirectional"))
    )
    (net (code "118") (name "unconnected-(U$1-Pad29)") (class "Default")
      (node (ref "U$1") (pin "29") (pinfunction "29_29") (pintype "bidirectional"))
    )
    (net (code "119") (name "unconnected-(U$1-Pad30)") (class "Default")
      (node (ref "U$1") (pin "30") (pinfunction "30_30") (pintype "bidirectional"))
    )
    (net (code "120") (name "unconnected-(U$1-Pad31)") (class "Default")
      (node (ref "U$1") (pin "31") (pinfunction "31_31") (pintype "bidirectional"))
    )
    (net (code "121") (name "unconnected-(U$1-Pad33)") (class "Default")
      (node (ref "U$1") (pin "33") (pinfunction "33_33") (pintype "bidirectional"))
    )
    (net (code "122") (name "unconnected-(U$1-Pad34)") (class "Default")
      (node (ref "U$1") (pin "34") (pinfunction "34_34") (pintype "bidirectional"))
    )
    (net (code "123") (name "unconnected-(U$1-Pad35)") (class "Default")
      (node (ref "U$1") (pin "35") (pinfunction "35_35") (pintype "bidirectional"))
    )
    (net (code "124") (name "unconnected-(U$1-Pad36)") (class "Default")
      (node (ref "U$1") (pin "36") (pinfunction "36_36") (pintype "bidirectional"))
    )
    (net (code "125") (name "unconnected-(U$1-Pad37)") (class "Default")
      (node (ref "U$1") (pin "37") (pinfunction "37_37") (pintype "bidirectional"))
    )
    (net (code "126") (name "unconnected-(U$1-Pad38)") (class "Default")
      (node (ref "U$1") (pin "38") (pinfunction "38_38") (pintype "bidirectional"))
    )
    (net (code "127") (name "unconnected-(U$1-Pad39)") (class "Default")
      (node (ref "U$1") (pin "39") (pinfunction "39_39") (pintype "bidirectional"))
    )
    (net (code "128") (name "unconnected-(U$1-Pad40)") (class "Default")
      (node (ref "U$1") (pin "40") (pinfunction "40_40") (pintype "bidirectional"))
    )
    (net (code "129") (name "unconnected-(U$1-Pad41)") (class "Default")
      (node (ref "U$1") (pin "41") (pinfunction "41_41") (pintype "bidirectional"))
    )
    (net (code "130") (name "unconnected-(U$1-Pad42)") (class "Default")
      (node (ref "U$1") (pin "42") (pinfunction "42_42") (pintype "bidirectional"))
    )
    (net (code "131") (name "unconnected-(U$1-Pad43)") (class "Default")
      (node (ref "U$1") (pin "43") (pinfunction "43_43") (pintype "bidirectional"))
    )
    (net (code "132") (name "unconnected-(U$1-Pad44)") (class "Default")
      (node (ref "U$1") (pin "44") (pinfunction "44_44") (pintype "bidirectional"))
    )
    (net (code "133") (name "unconnected-(U$1-Pad45)") (class "Default")
      (node (ref "U$1") (pin "45") (pinfunction "45_45") (pintype "bidirectional"))
    )
    (net (code "134") (name "unconnected-(U$1-Pad46)") (class "Default")
      (node (ref "U$1") (pin "46") (pinfunction "46_46") (pintype "bidirectional"))
    )
    (net (code "135") (name "unconnected-(U$1-Pad47)") (class "Default")
      (node (ref "U$1") (pin "47") (pinfunction "47_47") (pintype "bidirectional"))
    )
    (net (code "136") (name "unconnected-(U$1-Pad48)") (class "Default")
      (node (ref "U$1") (pin "48") (pinfunction "48_48") (pintype "bidirectional"))
    )
    (net (code "137") (name "unconnected-(U$1-Pad49)") (class "Default")
      (node (ref "U$1") (pin "49") (pinfunction "49_49") (pintype "bidirectional"))
    )
    (net (code "138") (name "unconnected-(U$1-Pad50)") (class "Default")
      (node (ref "U$1") (pin "50") (pinfunction "50_50") (pintype "bidirectional"))
    )
    (net (code "139") (name "unconnected-(U$1-Pad51)") (class "Default")
      (node (ref "U$1") (pin "51") (pinfunction "51_51") (pintype "bidirectional"))
    )
    (net (code "140") (name "unconnected-(U$1-PadA1)") (class "Default")
      (node (ref "U$1") (pin "A1") (pinfunction "A1_A1") (pintype "bidirectional"))
    )
    (net (code "141") (name "unconnected-(U$1-PadA2)") (class "Default")
      (node (ref "U$1") (pin "A2") (pinfunction "A2_A2") (pintype "bidirectional"))
    )
    (net (code "142") (name "unconnected-(U$1-PadA3)") (class "Default")
      (node (ref "U$1") (pin "A3") (pinfunction "A3_A3") (pintype "bidirectional"))
    )
    (net (code "143") (name "unconnected-(U$1-PadA6)") (class "Default")
      (node (ref "U$1") (pin "A6") (pinfunction "A6_A6") (pintype "bidirectional"))
    )
    (net (code "144") (name "unconnected-(U$1-PadA7)") (class "Default")
      (node (ref "U$1") (pin "A7") (pinfunction "A7_A7") (pintype "bidirectional"))
    )
    (net (code "145") (name "unconnected-(U$1-PadA8)") (class "Default")
      (node (ref "U$1") (pin "A8") (pinfunction "A8_A8") (pintype "bidirectional"))
    )
    (net (code "146") (name "unconnected-(U$1-PadA9)") (class "Default")
      (node (ref "U$1") (pin "A9") (pinfunction "A9_A9") (pintype "bidirectional"))
    )
    (net (code "147") (name "unconnected-(U$1-PadA10)") (class "Default")
      (node (ref "U$1") (pin "A10") (pinfunction "A10_A10") (pintype "bidirectional"))
    )
    (net (code "148") (name "unconnected-(U$1-PadA11)") (class "Default")
      (node (ref "U$1") (pin "A11") (pinfunction "A11_A11") (pintype "bidirectional"))
    )
    (net (code "149") (name "unconnected-(U$1-PadAREF)") (class "Default")
      (node (ref "U$1") (pin "AREF") (pinfunction "AREF_AREF") (pintype "bidirectional"))
    )
    (net (code "150") (name "unconnected-(U$1-PadRESET.)") (class "Default")
      (node (ref "U$1") (pin "RESET.") (pinfunction "RESET._RESET.") (pintype "bidirectional"))
    )
    (net (code "151") (name "unconnected-(U1-DNC-Pad7)") (class "Default")
      (node (ref "U1") (pin "7") (pinfunction "DNC_7") (pintype "passive"))
    )
    (net (code "152") (name "unconnected-(U1-DUPLED-Pad26)") (class "Default")
      (node (ref "U1") (pin "26") (pinfunction "DUPLED_26") (pintype "passive"))
    )
    (net (code "153") (name "unconnected-(U1-NC-Pad12)") (class "Default")
      (node (ref "U1") (pin "12") (pinfunction "NC_12") (pintype "passive"))
    )
    (net (code "154") (name "unconnected-(U1-NC-Pad13)") (class "Default")
      (node (ref "U1") (pin "13") (pinfunction "NC_13") (pintype "passive"))
    )
    (net (code "155") (name "unconnected-(U1-NC-Pad46)") (class "Default")
      (node (ref "U1") (pin "46") (pinfunction "NC_46") (pintype "passive"))
    )
    (net (code "156") (name "unconnected-(U1-NC-Pad47)") (class "Default")
      (node (ref "U1") (pin "47") (pinfunction "NC_47") (pintype "passive"))
    )
    (net (code "157") (name "unconnected-(U1-SPDLED-Pad24)") (class "Default")
      (node (ref "U1") (pin "24") (pinfunction "SPDLED_24") (pintype "passive"))
    )
    (net (code "158") (name "unconnected-(U1-VBG-Pad18)") (class "Default")
      (node (ref "U1") (pin "18") (pinfunction "VBG_18") (pintype "passive"))
    )
    (net (code "159") (name "unconnected-(XB1-AD0{slash}DIO0-Pad20)") (class "Default")
      (node (ref "XB1") (pin "20") (pinfunction "AD0/DIO0_20") (pintype "bidirectional"))
    )
    (net (code "160") (name "unconnected-(XB1-AD1{slash}DIO1-Pad19)") (class "Default")
      (node (ref "XB1") (pin "19") (pinfunction "AD1/DIO1_19") (pintype "bidirectional"))
    )
    (net (code "161") (name "unconnected-(XB1-AD2{slash}DIO2-Pad18)") (class "Default")
      (node (ref "XB1") (pin "18") (pinfunction "AD2/DIO2_18") (pintype "bidirectional"))
    )
    (net (code "162") (name "unconnected-(XB1-ASSOC{slash}AD5{slash}DIO5-Pad15)") (class "Default")
      (node (ref "XB1") (pin "15") (pinfunction "ASSOC/AD5/DIO5_15") (pintype "bidirectional"))
    )
    (net (code "163") (name "unconnected-(XB1-CD{slash}DOUT_EN{slash}DO8-Pad4)") (class "Default")
      (node (ref "XB1") (pin "4") (pinfunction "CD/DOUT_EN/DO8_4") (pintype "output"))
    )
    (net (code "164") (name "unconnected-(XB1-COORD_SEL{slash}AD3{slash}DIO3-Pad17)") (class "Default")
      (node (ref "XB1") (pin "17") (pinfunction "COORD_SEL/AD3/DIO3_17") (pintype "bidirectional"))
    )
    (net (code "165") (name "unconnected-(XB1-ON{slash}~{SLEEP}-Pad13)") (class "Default")
      (node (ref "XB1") (pin "13") (pinfunction "ON/~{SLEEP}_13") (pintype "output"))
    )
    (net (code "166") (name "unconnected-(XB1-PWM0{slash}RSSI-Pad6)") (class "Default")
      (node (ref "XB1") (pin "6") (pinfunction "PWM0/RSSI_6") (pintype "output"))
    )
    (net (code "167") (name "unconnected-(XB1-RF_TX{slash}AD4{slash}DIO4-Pad11)") (class "Default")
      (node (ref "XB1") (pin "11") (pinfunction "RF_TX/AD4/DIO4_11") (pintype "bidirectional"))
    )
    (net (code "168") (name "unconnected-(XB1-VREF-Pad14)") (class "Default")
      (node (ref "XB1") (pin "14") (pinfunction "VREF_14") (pintype "input"))
    )
  )
)
